# 3_MCU_Main.net
KiCad netlist of a schematic drawn in Altium Designer
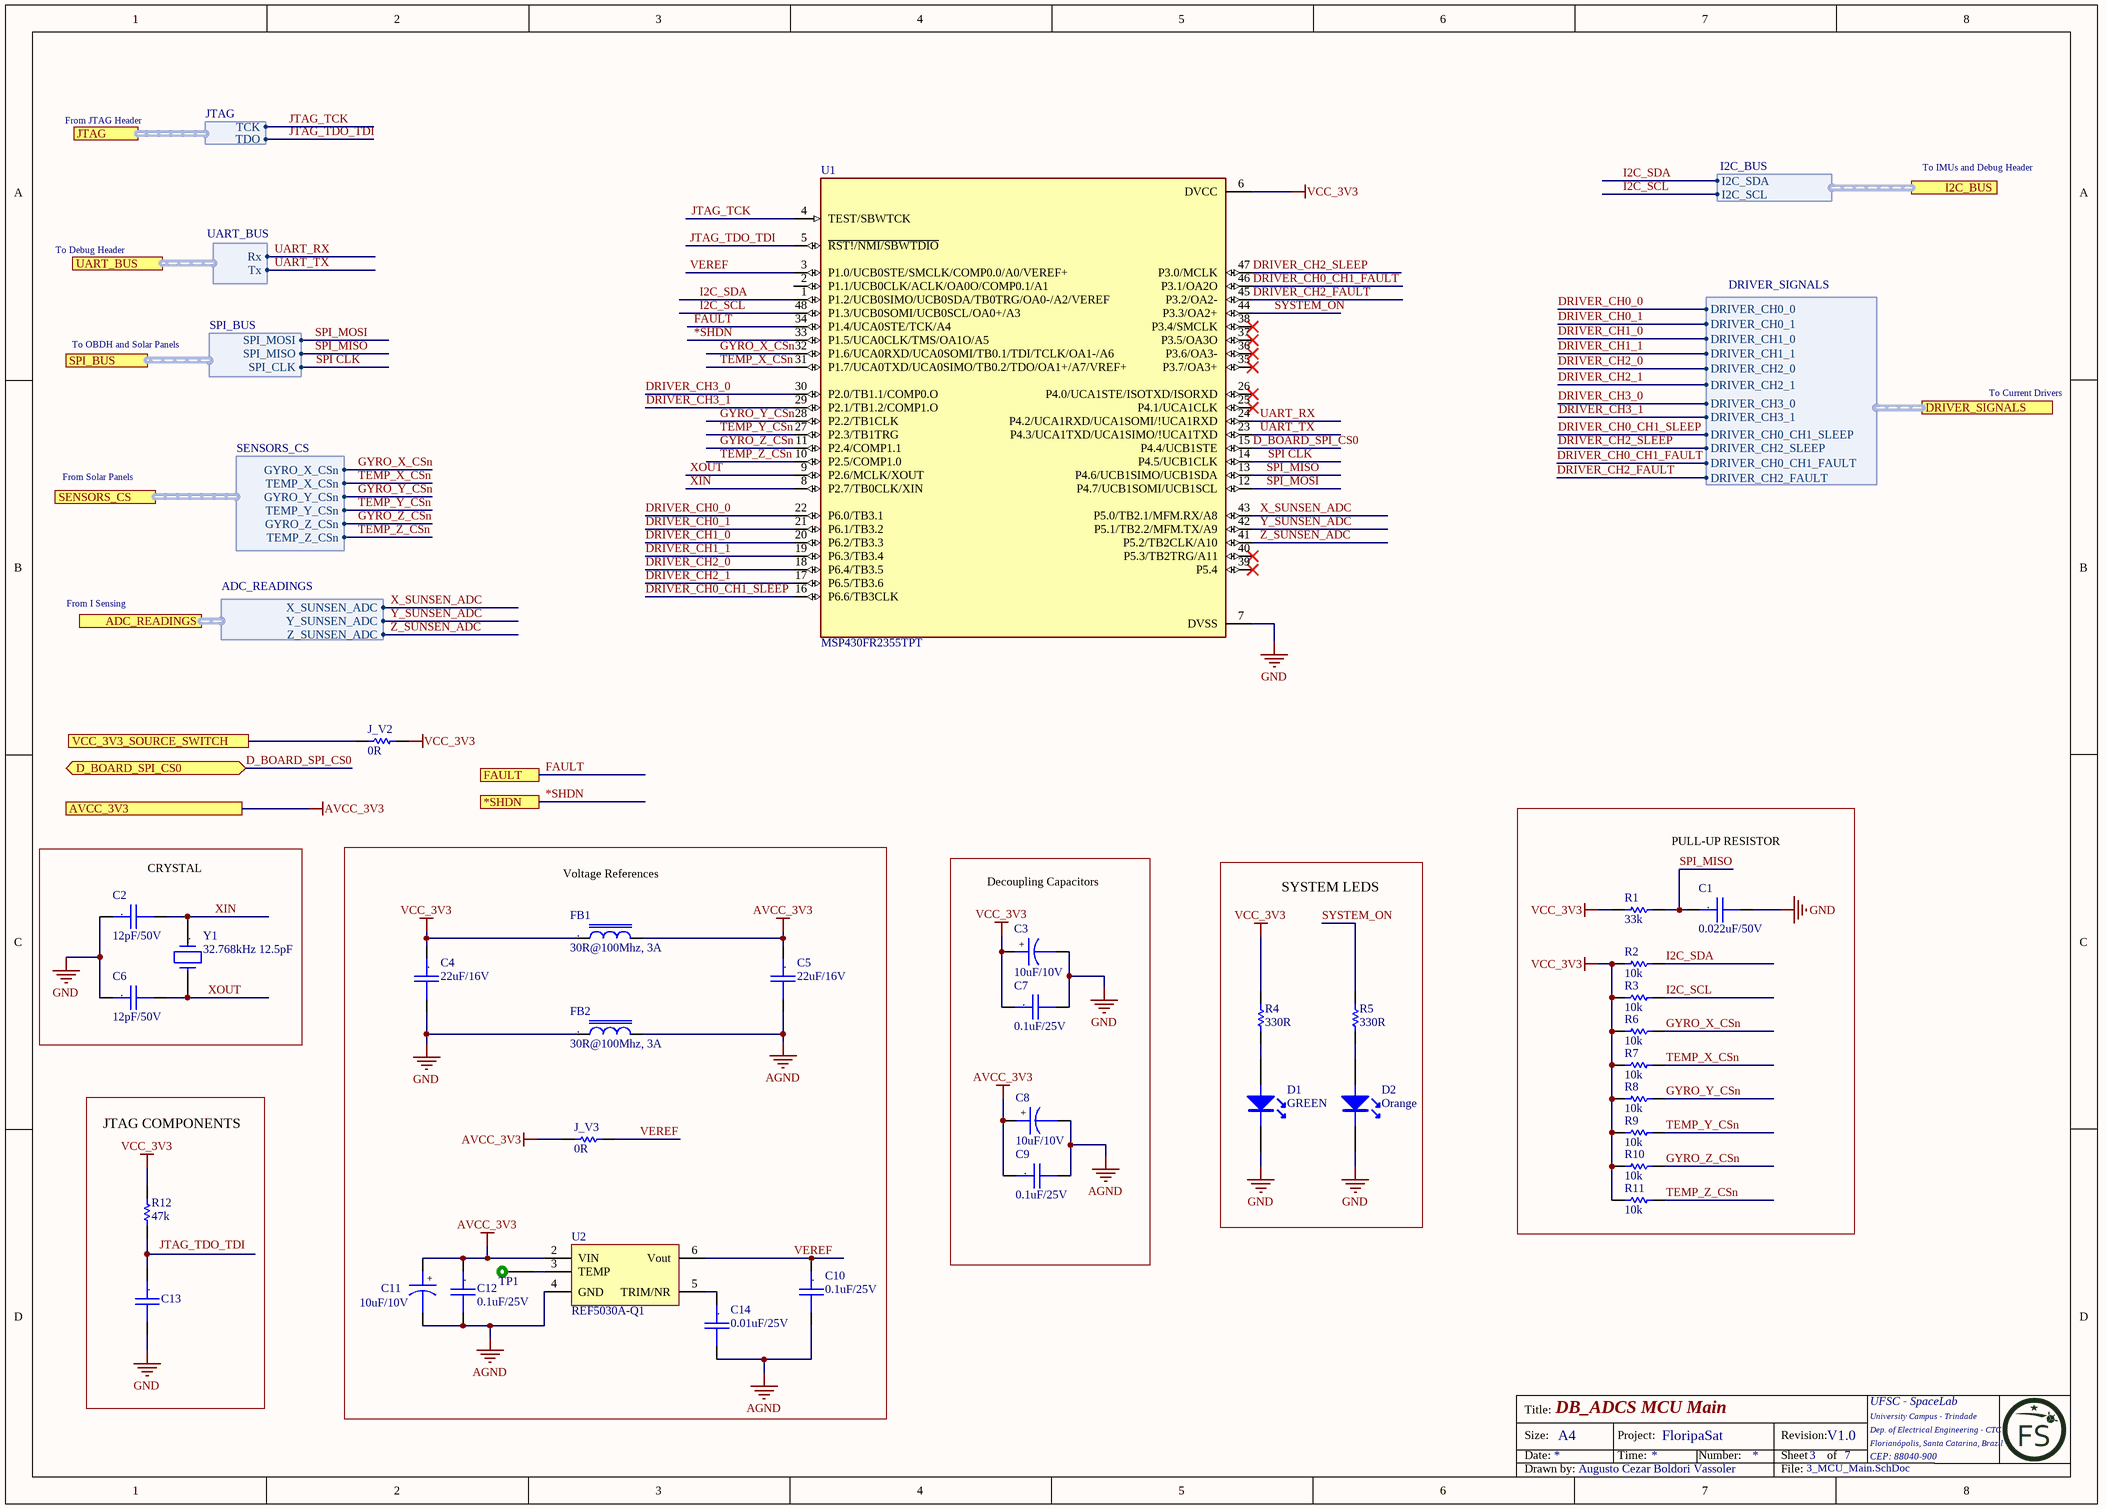
[diagram p0: 3_MCU_Main.SchDoc]

(export (version "E")
  (design (tool "Eeschema 10.0.6"))
  (components
    (comp (ref "C1")
      (value "0.022uF/50V")
      (footprint "CC0805")
      (description "CAP CER 0.022UF 50V 5% X7R 0805")
      (fields (field (name "PARTNUMBER") "CGA4J2C0G1H223J125AA"))
      (libsource (lib "PCB_Eng_Model_OBDH_2") (part "Cap_Cer_X7R_0.022uF_50V_0805"))
    )
    (comp (ref "C2")
      (value "12pF/50V")
      (footprint "CC0805")
      (description "CAP CER 12pF 50V 0805")
      (fields (field (name "PARTNUMBER") "CL21C120FBANNNC"))
      (libsource (lib "PCB_Eng_Model_OBDH_2") (part "Cap_Cer_X7R_12pF_50V_0805"))
    )
    (comp (ref "C3")
      (value "10uF/10V")
      (footprint "CC0805_Tantalum")
      (description "CAP Tantalum 10uF 6.3V 10% 0805")
      (fields (field (name "PARTNUMBER") "TPSR106K006R1000"))
      (libsource (lib "PCB_Eng_Model_OBDH_2") (part "Cap_Tant_SMD_10uF_6V3_0805"))
    )
    (comp (ref "C4")
      (value "22uF/16V")
      (footprint "CC1210")
      (description "CAP CER 22uF 16V 10% X7R 1210")
      (fields (field (name "PARTNUMBER") "C3225X7R1C226K250AC"))
      (libsource (lib "PCB_Eng_Model_OBDH_2") (part "Cap_Cer_X7R_0.01uF_16V_1210"))
    )
    (comp (ref "C5")
      (value "22uF/16V")
      (footprint "CC1210")
      (description "CAP CER 22uF 16V 10% X7R 1210")
      (fields (field (name "PARTNUMBER") "C3225X7R1C226K250AC"))
      (libsource (lib "PCB_Eng_Model_OBDH_2") (part "Cap_Cer_X7R_0.01uF_16V_1210"))
    )
    (comp (ref "C6")
      (value "12pF/50V")
      (footprint "CC0805")
      (description "CAP CER 12pF 50V 0805")
      (fields (field (name "PARTNUMBER") "CL21C120FBANNNC"))
      (libsource (lib "PCB_Eng_Model_OBDH_2") (part "Cap_Cer_X7R_12pF_50V_0805"))
    )
    (comp (ref "C7")
      (value "0.1uF/25V")
      (footprint "CC0805")
      (description "CAP CER 0.1UF 25V 10% X7R 0805")
      (fields (field (name "PARTNUMBER") "CC0805KRX7R8BB104"))
      (libsource (lib "PCB_Eng_Model_OBDH_2") (part "Cap_Cer_X7R_0.1uF_25V_0805"))
    )
    (comp (ref "C8")
      (value "10uF/10V")
      (footprint "CC0805_Tantalum")
      (description "CAP Tantalum 10uF 6.3V 10% 0805")
      (fields (field (name "PARTNUMBER") "TPSR106K006R1000"))
      (libsource (lib "PCB_Eng_Model_OBDH_2") (part "Cap_Tant_SMD_10uF_6V3_0805"))
    )
    (comp (ref "C9")
      (value "0.1uF/25V")
      (footprint "CC0805")
      (description "CAP CER 0.1UF 25V 10% X7R 0805")
      (fields (field (name "PARTNUMBER") "CC0805KRX7R8BB104"))
      (libsource (lib "PCB_Eng_Model_OBDH_2") (part "Cap_Cer_X7R_0.1uF_25V_0805"))
    )
    (comp (ref "C10")
      (value "0.1uF/25V")
      (footprint "CC0805")
      (description "CAP CER 0.1UF 25V 10% X7R 0805")
      (fields (field (name "PARTNUMBER") "CC0805KRX7R8BB104"))
      (libsource (lib "PCB_Eng_Model_OBDH_2") (part "Cap_Cer_X7R_0.1uF_25V_0805"))
    )
    (comp (ref "C11")
      (value "10uF/10V")
      (footprint "CC0805_Tantalum")
      (description "CAP Tantalum 10uF 6.3V 10% 0805")
      (fields (field (name "PARTNUMBER") "TPSR106K006R1000"))
      (libsource (lib "PCB_Eng_Model_OBDH_2") (part "Cap_Tant_SMD_10uF_6V3_0805"))
    )
    (comp (ref "C12")
      (value "0.1uF/25V")
      (footprint "CC0805")
      (description "CAP CER 0.1UF 25V 10% X7R 0805")
      (fields (field (name "PARTNUMBER") "CC0805KRX7R8BB104"))
      (libsource (lib "PCB_Eng_Model_OBDH_2") (part "Cap_Cer_X7R_0.1uF_25V_0805"))
    )
    (comp (ref "C13")
      (value "1nF/50V")
      (footprint "CC0805")
      (description "0805 1 nF 50V ±10 % Tolerance X7R Surface Mount Multilayer Ceramic Capacitor")
      (fields
        (field (name "MANUFACTURER") "Kyocera AVX")
        (field (name "MANUFACTURER PART NUMBER") "08055C102KAT2A")
      )
      (libsource (lib "PCB_Eng_Model_OBDH_2") (part "Cap_Cer_X7R_0.001uF_50V_0805"))
    )
    (comp (ref "C14")
      (value "0.01uF/25V")
      (footprint "CC0805")
      (description "CAP CER 0.01uF 25V 10% X7R 0805")
      (fields (field (name "PARTNUMBER") "CL21B103KAANNNC"))
      (libsource (lib "PCB_Eng_Model_OBDH_2") (part "Cap_Cer_X7R_0.01uF_50V_0805"))
    )
    (comp (ref "D1")
      (value "GREEN")
      (footprint "0805-LED")
      (description "SMD Green LED")
      (fields (field (name "PARTNUMBER") "LTST-C171GKT"))
      (libsource (lib "PCB_Eng_Model_OBDH_2") (part "LED/G_0805"))
    )
    (comp (ref "D2")
      (value "Orange")
      (footprint "0805-LED")
      (description "SMD Orange LED")
      (fields (field (name "PARTNUMBER") "LTST-C170KFKT"))
      (libsource (lib "PCB_Eng_Model_OBDH_2") (part "LED/R_0603"))
    )
    (comp (ref "FB1")
      (value "30R@100Mhz, 3A")
      (footprint "IND0805")
      (description "Ferrite Bead 30 OHM 3A 100MHz")
      (fields (field (name "PARTNUMBER") "BLM21PG300SN1D"))
      (libsource (lib "PCB_Eng_Model_OBDH_2") (part "FB_30R_3A_100MHz_0805"))
    )
    (comp (ref "FB2")
      (value "30R@100Mhz, 3A")
      (footprint "IND0805")
      (description "Ferrite Bead 30 OHM 3A 100MHz")
      (fields (field (name "PARTNUMBER") "BLM21PG300SN1D"))
      (libsource (lib "PCB_Eng_Model_OBDH_2") (part "FB_30R_3A_100MHz_0805"))
    )
    (comp (ref "J_V2")
      (value "0R")
      (footprint "0805-LED")
      (description "RES 0R OHM 1/16W JUMPER 0805")
      (fields (field (name "PARTNUMBER") "CRCW08050000Z0EA"))
      (libsource (lib "PCB_Eng_Model_OBDH_2") (part "R0R_JUMPER_1/16W_0805"))
    )
    (comp (ref "J_V3")
      (value "0R")
      (footprint "0805-LED")
      (description "RES 0R OHM 1/16W JUMPER 0805")
      (fields (field (name "PARTNUMBER") "CRCW08050000Z0EA"))
      (libsource (lib "PCB_Eng_Model_OBDH_2") (part "R0R_JUMPER_1/16W_0805"))
    )
    (comp (ref "R1")
      (value "33k")
      (footprint "0805")
      (description "RES 33K OHM 1/10W 1% 0805")
      (fields (field (name "PARTNUMBER") "RC0805FR-0733KL"))
      (libsource (lib "PCB_Eng_Model_OBDH_2") (part "R33k_1%_1/10W_0805"))
    )
    (comp (ref "R2")
      (value "10k")
      (footprint "0805")
      (description "RES 10K OHM 1/8W 1%  0805")
      (fields (field (name "PARTNUMBER") "CRCW080510K0FKEA"))
      (libsource (lib "PCB_Eng_Model_OBDH_2") (part "R10k_1%_1/8W_0805"))
    )
    (comp (ref "R3")
      (value "10k")
      (footprint "0805")
      (description "RES 10K OHM 1/8W 1%  0805")
      (fields (field (name "PARTNUMBER") "CRCW080510K0FKEA"))
      (libsource (lib "PCB_Eng_Model_OBDH_2") (part "R10k_1%_1/8W_0805"))
    )
    (comp (ref "R4")
      (value "330R")
      (footprint "0805")
      (description "RES 330R OHM 1/4W 1% 0805")
      (fields (field (name "PARTNUMBER") "RC0805FR-07330RL"))
      (libsource (lib "PCB_Eng_Model_OBDH_2") (part "R330R_1%_1/4W_0805"))
    )
    (comp (ref "R5")
      (value "330R")
      (footprint "0805")
      (description "RES 330R OHM 1/4W 1% 0805")
      (fields (field (name "PARTNUMBER") "RC0805FR-07330RL"))
      (libsource (lib "PCB_Eng_Model_OBDH_2") (part "R330R_1%_1/4W_0805"))
    )
    (comp (ref "R6")
      (value "10k")
      (footprint "0805")
      (description "RES 10K OHM 1/8W 1%  0805")
      (fields (field (name "PARTNUMBER") "CRCW080510K0FKEA"))
      (libsource (lib "PCB_Eng_Model_OBDH_2") (part "R10k_1%_1/8W_0805"))
    )
    (comp (ref "R7")
      (value "10k")
      (footprint "0805")
      (description "RES 10K OHM 1/8W 1%  0805")
      (fields (field (name "PARTNUMBER") "CRCW080510K0FKEA"))
      (libsource (lib "PCB_Eng_Model_OBDH_2") (part "R10k_1%_1/8W_0805"))
    )
    (comp (ref "R8")
      (value "10k")
      (footprint "0805")
      (description "RES 10K OHM 1/8W 1%  0805")
      (fields (field (name "PARTNUMBER") "CRCW080510K0FKEA"))
      (libsource (lib "PCB_Eng_Model_OBDH_2") (part "R10k_1%_1/8W_0805"))
    )
    (comp (ref "R9")
      (value "10k")
      (footprint "0805")
      (description "RES 10K OHM 1/8W 1%  0805")
      (fields (field (name "PARTNUMBER") "CRCW080510K0FKEA"))
      (libsource (lib "PCB_Eng_Model_OBDH_2") (part "R10k_1%_1/8W_0805"))
    )
    (comp (ref "R10")
      (value "10k")
      (footprint "0805")
      (description "RES 10K OHM 1/8W 1%  0805")
      (fields (field (name "PARTNUMBER") "CRCW080510K0FKEA"))
      (libsource (lib "PCB_Eng_Model_OBDH_2") (part "R10k_1%_1/8W_0805"))
    )
    (comp (ref "R11")
      (value "10k")
      (footprint "0805")
      (description "RES 10K OHM 1/8W 1%  0805")
      (fields (field (name "PARTNUMBER") "CRCW080510K0FKEA"))
      (libsource (lib "PCB_Eng_Model_OBDH_2") (part "R10k_1%_1/8W_0805"))
    )
    (comp (ref "R12")
      (value "47k")
      (footprint "0805")
      (description "RES 47k OHM 1/10W 1% 0805")
      (fields (field (name "PARTNUMBER") "RC0805FR-0747KL"))
      (libsource (lib "PCB_DB_ADCS") (part "R27_5%_1/10W_0805"))
    )
    (comp (ref "TP1")
      (value "TEST_POINT_2")
      (footprint "TEST_POINT_2")
      (description "Test point")
      (libsource (lib "PCB_Eng_Model_OBDH_2") (part "TEST_POINT_2"))
    )
    (comp (ref "U1")
      (value "MSP430FR2355TPT")
      (footprint "QFP50P900X900X160-48N - duplicate")
      (description "CPU16 MSP430â„¢ FRAM Microcontroller IC 16-Bit 24MHz 32KB _32K x 8_ FRAM 48-LQFP _7x7_")
      (fields (field (name "MF") "Texas Instruments"))
      (libsource (lib "PCB_Eng_Model_OBDH_2") (part "MSP430FR2355TPT"))
    )
    (comp (ref "U2")
      (value "REF5030A-Q1")
      (footprint "SOIC-8")
      (libsource (lib "PCB_Eng_Model_OBDH_2") (part "REF5030A-Q1"))
    )
    (comp (ref "Y1")
      (value "32.768kHz 12.5pF")
      (footprint "ABS06 0805")
      (description "32.768kHz ±20ppm Crystal 12.5pF 70 kOhm -40°C ~ 125°C")
      (fields (field (name "PARTNUMBER") "ECS-.327-12.5-34S-TR"))
      (libsource (lib "PCB_Eng_Model_OBDH_2") (part "Xtal_32.768kHz_12pF_2_SMD"))
    )
  )
  (nets
    (net (code "8") (name "/*SHDN") (class "Default")
      (node (ref "U1") (pin "33") (pinfunction "P1.5/UCA0CLK/TMS/OA1O/A5_33") (pintype "bidirectional"))
    )
    (net (code "9") (name "/DRIVER_CH0_0") (class "Default")
      (node (ref "U1") (pin "22") (pinfunction "P6.0/TB3.1_22") (pintype "bidirectional"))
    )
    (net (code "10") (name "/DRIVER_CH0_1") (class "Default")
      (node (ref "U1") (pin "21") (pinfunction "P6.1/TB3.2_21") (pintype "bidirectional"))
    )
    (net (code "11") (name "/DRIVER_CH0_CH1_FAULT") (class "Default")
      (node (ref "U1") (pin "46") (pinfunction "P3.1/OA2O_46") (pintype "bidirectional"))
    )
    (net (code "12") (name "/DRIVER_CH0_CH1_SLEEP") (class "Default")
      (node (ref "U1") (pin "16") (pinfunction "P6.6/TB3CLK_16") (pintype "bidirectional"))
    )
    (net (code "13") (name "/DRIVER_CH1_0") (class "Default")
      (node (ref "U1") (pin "20") (pinfunction "P6.2/TB3.3_20") (pintype "bidirectional"))
    )
    (net (code "14") (name "/DRIVER_CH1_1") (class "Default")
      (node (ref "U1") (pin "19") (pinfunction "P6.3/TB3.4_19") (pintype "bidirectional"))
    )
    (net (code "15") (name "/DRIVER_CH2_0") (class "Default")
      (node (ref "U1") (pin "18") (pinfunction "P6.4/TB3.5_18") (pintype "bidirectional"))
    )
    (net (code "16") (name "/DRIVER_CH2_1") (class "Default")
      (node (ref "U1") (pin "17") (pinfunction "P6.5/TB3.6_17") (pintype "bidirectional"))
    )
    (net (code "17") (name "/DRIVER_CH2_FAULT") (class "Default")
      (node (ref "U1") (pin "45") (pinfunction "P3.2/OA2-_45") (pintype "bidirectional"))
    )
    (net (code "18") (name "/DRIVER_CH2_SLEEP") (class "Default")
      (node (ref "U1") (pin "47") (pinfunction "P3.0/MCLK_47") (pintype "bidirectional"))
    )
    (net (code "19") (name "/DRIVER_CH3_0") (class "Default")
      (node (ref "U1") (pin "30") (pinfunction "P2.0/TB1.1/COMP0.O_30") (pintype "bidirectional"))
    )
    (net (code "20") (name "/DRIVER_CH3_1") (class "Default")
      (node (ref "U1") (pin "29") (pinfunction "P2.1/TB1.2/COMP1.O_29") (pintype "bidirectional"))
    )
    (net (code "21") (name "/D_BOARD_SPI_CS0") (class "Default")
      (node (ref "U1") (pin "15") (pinfunction "P4.4/UCB1STE_15") (pintype "bidirectional"))
    )
    (net (code "22") (name "/FAULT") (class "Default")
      (node (ref "U1") (pin "34") (pinfunction "P1.4/UCA0STE/TCK/A4_34") (pintype "bidirectional"))
    )
    (net (code "23") (name "/GYRO_X_CSn") (class "Default")
      (node (ref "R6") (pin "1") (pinfunction "1_1") (pintype "passive"))
      (node (ref "U1") (pin "32") (pinfunction "P1.6/UCA0RXD/UCA0SOMI/TB0.1/TDI/TCLK/OA1-/A6_32") (pintype "bidirectional"))
    )
    (net (code "24") (name "/GYRO_Y_CSn") (class "Default")
      (node (ref "R8") (pin "1") (pinfunction "1_1") (pintype "passive"))
      (node (ref "U1") (pin "28") (pinfunction "P2.2/TB1CLK_28") (pintype "bidirectional"))
    )
    (net (code "25") (name "/GYRO_Z_CSn") (class "Default")
      (node (ref "R10") (pin "1") (pinfunction "1_1") (pintype "passive"))
      (node (ref "U1") (pin "11") (pinfunction "P2.4/COMP1.1_11") (pintype "bidirectional"))
    )
    (net (code "26") (name "/I2C_SCL") (class "Default")
      (node (ref "R3") (pin "1") (pinfunction "1_1") (pintype "passive"))
      (node (ref "U1") (pin "48") (pinfunction "P1.3/UCB0SOMI/UCB0SCL/OA0+/A3_48") (pintype "bidirectional"))
    )
    (net (code "27") (name "/I2C_SDA") (class "Default")
      (node (ref "R2") (pin "1") (pinfunction "1_1") (pintype "passive"))
      (node (ref "U1") (pin "1") (pinfunction "P1.2/UCB0SIMO/UCB0SDA/TB0TRG/OA0-/A2/VEREF_1") (pintype "bidirectional"))
    )
    (net (code "28") (name "/JTAG_TCK") (class "Default")
      (node (ref "U1") (pin "4") (pinfunction "TEST/SBWTCK_4") (pintype "input"))
    )
    (net (code "29") (name "/JTAG_TDO_TDI") (class "Default")
      (node (ref "U1") (pin "5") (pinfunction "~{RST!/NMI/SBWTDIO}_5") (pintype "bidirectional"))
    )
    (net (code "30") (name "/SPI CLK") (class "Default")
      (node (ref "U1") (pin "14") (pinfunction "P4.5/UCB1CLK_14") (pintype "bidirectional"))
    )
    (net (code "31") (name "/SPI_MISO") (class "Default")
      (node (ref "C1") (pin "1") (pinfunction "1_1") (pintype "passive"))
      (node (ref "R1") (pin "1") (pinfunction "1_1") (pintype "passive"))
      (node (ref "U1") (pin "13") (pinfunction "P4.6/UCB1SIMO/UCB1SDA_13") (pintype "bidirectional"))
    )
    (net (code "32") (name "/SPI_MOSI") (class "Default")
      (node (ref "U1") (pin "12") (pinfunction "P4.7/UCB1SOMI/UCB1SCL_12") (pintype "bidirectional"))
    )
    (net (code "33") (name "/SYSTEM_ON") (class "Default")
      (node (ref "R5") (pin "2") (pinfunction "2_2") (pintype "passive"))
      (node (ref "U1") (pin "44") (pinfunction "P3.3/OA2+_44") (pintype "bidirectional"))
    )
    (net (code "34") (name "/TEMP_X_CSn") (class "Default")
      (node (ref "R7") (pin "1") (pinfunction "1_1") (pintype "passive"))
      (node (ref "U1") (pin "31") (pinfunction "P1.7/UCA0TXD/UCA0SIMO/TB0.2/TDO/OA1+/A7/VREF+_31") (pintype "bidirectional"))
    )
    (net (code "35") (name "/TEMP_Y_CSn") (class "Default")
      (node (ref "R9") (pin "1") (pinfunction "1_1") (pintype "passive"))
      (node (ref "U1") (pin "27") (pinfunction "P2.3/TB1TRG_27") (pintype "bidirectional"))
    )
    (net (code "36") (name "/TEMP_Z_CSn") (class "Default")
      (node (ref "R11") (pin "1") (pinfunction "1_1") (pintype "passive"))
      (node (ref "U1") (pin "10") (pinfunction "P2.5/COMP1.0_10") (pintype "bidirectional"))
    )
    (net (code "37") (name "/UART_RX") (class "Default")
      (node (ref "U1") (pin "24") (pinfunction "P4.2/UCA1RXD/UCA1SOMI/!UCA1RXD_24") (pintype "bidirectional"))
    )
    (net (code "38") (name "/UART_TX") (class "Default")
      (node (ref "U1") (pin "23") (pinfunction "P4.3/UCA1TXD/UCA1SIMO/!UCA1TXD_23") (pintype "bidirectional"))
    )
    (net (code "39") (name "/VCC_3V3_SOURCE_SWITCH") (class "Default")
      (node (ref "J_V2") (pin "2") (pinfunction "2_2") (pintype "passive"))
    )
    (net (code "40") (name "/VEREF") (class "Default")
      (node (ref "C10") (pin "1") (pinfunction "1_1") (pintype "passive"))
      (node (ref "J_V3") (pin "1") (pinfunction "1_1") (pintype "passive"))
      (node (ref "U1") (pin "3") (pinfunction "P1.0/UCB0STE/SMCLK/COMP0.0/A0/VEREF+_3") (pintype "bidirectional"))
      (node (ref "U2") (pin "6") (pinfunction "Vout_6") (pintype "passive"))
    )
    (net (code "41") (name "/XIN") (class "Default")
      (node (ref "C2") (pin "2") (pinfunction "2_2") (pintype "passive"))
      (node (ref "U1") (pin "8") (pinfunction "P2.7/TB0CLK/XIN_8") (pintype "bidirectional"))
      (node (ref "Y1") (pin "1") (pinfunction "1_1") (pintype "passive"))
    )
    (net (code "42") (name "/XOUT") (class "Default")
      (node (ref "C6") (pin "2") (pinfunction "2_2") (pintype "passive"))
      (node (ref "U1") (pin "9") (pinfunction "P2.6/MCLK/XOUT_9") (pintype "bidirectional"))
      (node (ref "Y1") (pin "2") (pinfunction "2_2") (pintype "passive"))
    )
    (net (code "43") (name "/X_SUNSEN_ADC") (class "Default")
      (node (ref "U1") (pin "43") (pinfunction "P5.0/TB2.1/MFM.RX/A8_43") (pintype "bidirectional"))
    )
    (net (code "44") (name "/Y_SUNSEN_ADC") (class "Default")
      (node (ref "U1") (pin "42") (pinfunction "P5.1/TB2.2/MFM.TX/A9_42") (pintype "bidirectional"))
    )
    (net (code "45") (name "/Z_SUNSEN_ADC") (class "Default")
      (node (ref "U1") (pin "41") (pinfunction "P5.2/TB2CLK/A10_41") (pintype "bidirectional"))
    )
    (net (code "53") (name "AGND") (class "Default")
      (node (ref "C10") (pin "2") (pinfunction "2_2") (pintype "passive"))
      (node (ref "C11") (pin "2") (pinfunction "2_2") (pintype "passive"))
      (node (ref "C12") (pin "2") (pinfunction "2_2") (pintype "passive"))
      (node (ref "C14") (pin "2") (pinfunction "2_2") (pintype "passive"))
      (node (ref "C5") (pin "2") (pinfunction "2_2") (pintype "passive"))
      (node (ref "C8") (pin "2") (pinfunction "2_2") (pintype "passive"))
      (node (ref "C9") (pin "2") (pinfunction "2_2") (pintype "passive"))
      (node (ref "FB2") (pin "2") (pinfunction "2_2") (pintype "passive"))
      (node (ref "U2") (pin "4") (pinfunction "GND_4") (pintype "passive"))
    )
    (net (code "54") (name "AVCC_3V3") (class "Default")
      (node (ref "C11") (pin "1") (pinfunction "1_1") (pintype "passive"))
      (node (ref "C12") (pin "1") (pinfunction "1_1") (pintype "passive"))
      (node (ref "C5") (pin "1") (pinfunction "1_1") (pintype "passive"))
      (node (ref "C8") (pin "1") (pinfunction "1_1") (pintype "passive"))
      (node (ref "C9") (pin "1") (pinfunction "1_1") (pintype "passive"))
      (node (ref "FB1") (pin "2") (pinfunction "2_2") (pintype "passive"))
      (node (ref "J_V3") (pin "2") (pinfunction "2_2") (pintype "passive"))
      (node (ref "U2") (pin "2") (pinfunction "VIN_2") (pintype "passive"))
    )
    (net (code "55") (name "GND") (class "Default")
      (node (ref "C1") (pin "2") (pinfunction "2_2") (pintype "passive"))
      (node (ref "C13") (pin "2") (pinfunction "2_2") (pintype "passive"))
      (node (ref "C2") (pin "1") (pinfunction "1_1") (pintype "passive"))
      (node (ref "C3") (pin "2") (pinfunction "2_2") (pintype "passive"))
      (node (ref "C4") (pin "2") (pinfunction "2_2") (pintype "passive"))
      (node (ref "C6") (pin "1") (pinfunction "1_1") (pintype "passive"))
      (node (ref "C7") (pin "2") (pinfunction "2_2") (pintype "passive"))
      (node (ref "D1") (pin "2") (pinfunction "K_2") (pintype "passive"))
      (node (ref "D2") (pin "2") (pinfunction "K_2") (pintype "passive"))
      (node (ref "FB2") (pin "1") (pinfunction "1_1") (pintype "passive"))
      (node (ref "U1") (pin "7") (pinfunction "DVSS_7") (pintype "power_in"))
    )
    (net (code "56") (name "Net-(C13-Pad1)") (class "Default")
      (node (ref "C13") (pin "1") (pinfunction "1_1") (pintype "passive"))
      (node (ref "R12") (pin "1") (pinfunction "1_1") (pintype "passive"))
    )
    (net (code "57") (name "Net-(D1-A)") (class "Default")
      (node (ref "D1") (pin "1") (pinfunction "A_1") (pintype "passive"))
      (node (ref "R4") (pin "1") (pinfunction "1_1") (pintype "passive"))
    )
    (net (code "58") (name "Net-(D2-A)") (class "Default")
      (node (ref "D2") (pin "1") (pinfunction "A_1") (pintype "passive"))
      (node (ref "R5") (pin "1") (pinfunction "1_1") (pintype "passive"))
    )
    (net (code "59") (name "Net-(U2-TEMP)") (class "Default")
      (node (ref "TP1") (pin "1") (pinfunction "1_1") (pintype "passive"))
      (node (ref "U2") (pin "3") (pinfunction "TEMP_3") (pintype "passive"))
    )
    (net (code "60") (name "Net-(U2-TRIM{slash}NR)") (class "Default")
      (node (ref "C14") (pin "1") (pinfunction "1_1") (pintype "passive"))
      (node (ref "U2") (pin "5") (pinfunction "TRIM/NR_5") (pintype "passive"))
    )
    (net (code "61") (name "VCC_3V3") (class "Default")
      (node (ref "C3") (pin "1") (pinfunction "1_1") (pintype "passive"))
      (node (ref "C4") (pin "1") (pinfunction "1_1") (pintype "passive"))
      (node (ref "C7") (pin "1") (pinfunction "1_1") (pintype "passive"))
      (node (ref "FB1") (pin "1") (pinfunction "1_1") (pintype "passive"))
      (node (ref "J_V2") (pin "1") (pinfunction "1_1") (pintype "passive"))
      (node (ref "R1") (pin "2") (pinfunction "2_2") (pintype "passive"))
      (node (ref "R10") (pin "2") (pinfunction "2_2") (pintype "passive"))
      (node (ref "R11") (pin "2") (pinfunction "2_2") (pintype "passive"))
      (node (ref "R12") (pin "2") (pinfunction "2_2") (pintype "passive"))
      (node (ref "R2") (pin "2") (pinfunction "2_2") (pintype "passive"))
      (node (ref "R3") (pin "2") (pinfunction "2_2") (pintype "passive"))
      (node (ref "R4") (pin "2") (pinfunction "2_2") (pintype "passive"))
      (node (ref "R6") (pin "2") (pinfunction "2_2") (pintype "passive"))
      (node (ref "R7") (pin "2") (pinfunction "2_2") (pintype "passive"))
      (node (ref "R8") (pin "2") (pinfunction "2_2") (pintype "passive"))
      (node (ref "R9") (pin "2") (pinfunction "2_2") (pintype "passive"))
      (node (ref "U1") (pin "6") (pinfunction "DVCC_6") (pintype "power_in"))
    )
    (net (code "62") (name "unconnected-(U1-P1.1{slash}UCB0CLK{slash}ACLK{slash}OA0O{slash}COMP0.1{slash}A1-Pad2)") (class "Default")
      (node (ref "U1") (pin "2") (pinfunction "P1.1/UCB0CLK/ACLK/OA0O/COMP0.1/A1_2") (pintype "bidirectional"))
    )
    (net (code "63") (name "unconnected-(U1-P3.4{slash}SMCLK-Pad38)") (class "Default")
      (node (ref "U1") (pin "38") (pinfunction "P3.4/SMCLK_38") (pintype "bidirectional+no_connect"))
    )
    (net (code "64") (name "unconnected-(U1-P3.5{slash}OA3O-Pad37)") (class "Default")
      (node (ref "U1") (pin "37") (pinfunction "P3.5/OA3O_37") (pintype "bidirectional+no_connect"))
    )
    (net (code "65") (name "unconnected-(U1-P3.6{slash}OA3--Pad36)") (class "Default")
      (node (ref "U1") (pin "36") (pinfunction "P3.6/OA3-_36") (pintype "bidirectional+no_connect"))
    )
    (net (code "66") (name "unconnected-(U1-P3.7{slash}OA3+-Pad35)") (class "Default")
      (node (ref "U1") (pin "35") (pinfunction "P3.7/OA3+_35") (pintype "bidirectional+no_connect"))
    )
    (net (code "67") (name "unconnected-(U1-P4.0{slash}UCA1STE{slash}ISOTXD{slash}ISORXD-Pad26)") (class "Default")
      (node (ref "U1") (pin "26") (pinfunction "P4.0/UCA1STE/ISOTXD/ISORXD_26") (pintype "bidirectional+no_connect"))
    )
    (net (code "68") (name "unconnected-(U1-P4.1{slash}UCA1CLK-Pad25)") (class "Default")
      (node (ref "U1") (pin "25") (pinfunction "P4.1/UCA1CLK_25") (pintype "bidirectional+no_connect"))
    )
    (net (code "69") (name "unconnected-(U1-P5.3{slash}TB2TRG{slash}A11-Pad40)") (class "Default")
      (node (ref "U1") (pin "40") (pinfunction "P5.3/TB2TRG/A11_40") (pintype "bidirectional+no_connect"))
    )
    (net (code "70") (name "unconnected-(U1-P5.4-Pad39)") (class "Default")
      (node (ref "U1") (pin "39") (pinfunction "P5.4_39") (pintype "bidirectional+no_connect"))
    )
  )
)
